# 393.net
KiCad netlist of a schematic drawn in EAGLE
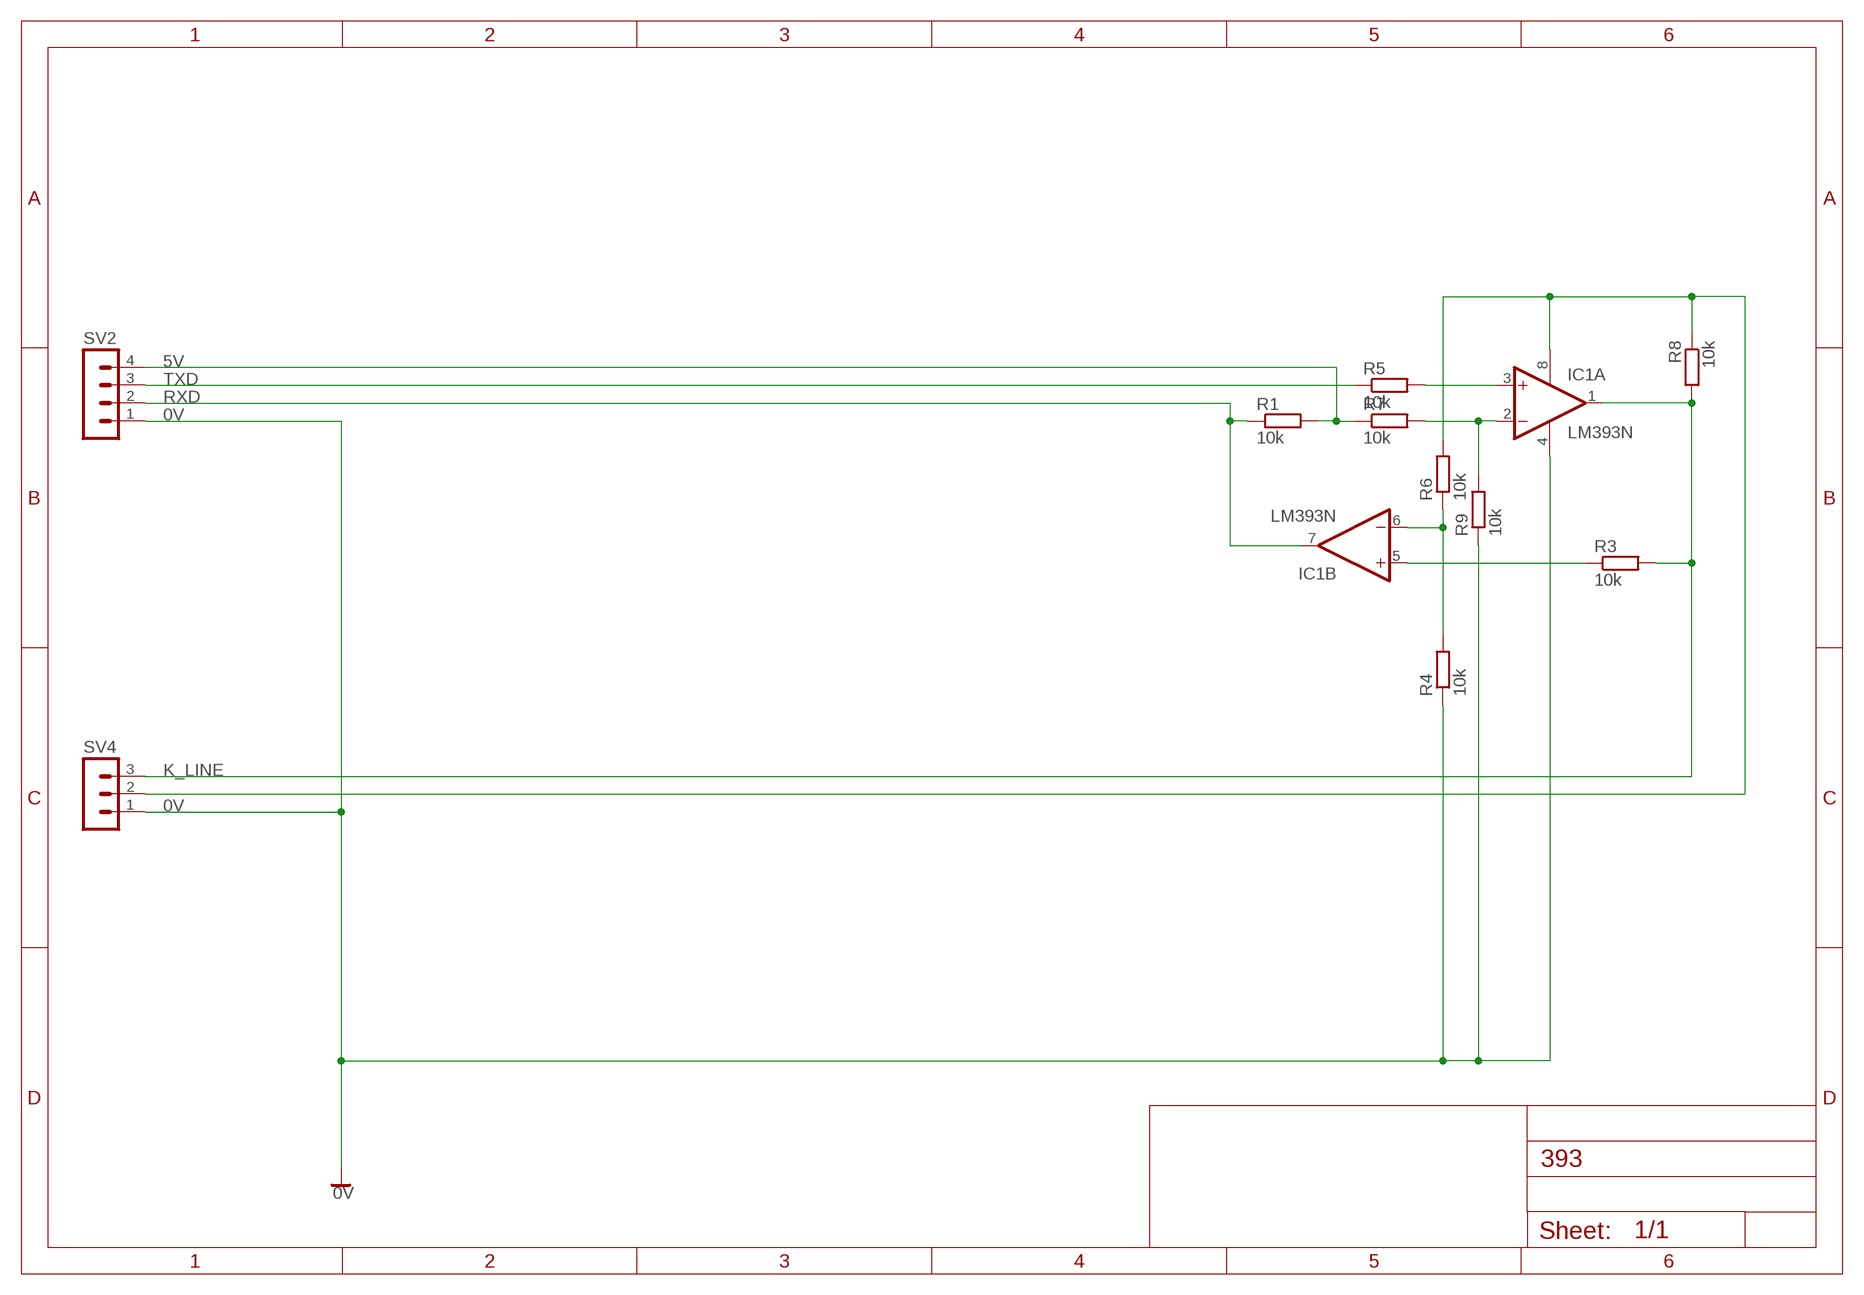
[diagram p0: schematic, sheet 1]

(export (version "E")
  (design (tool "Eeschema 10.0.6"))
  (components
    (comp (ref "IC1")
      (value "LM393N")
      (footprint "eagle-import:DIL08")
      (libsource (lib "eagle-import") (part "LM393N"))
    )
    (comp (ref "R1")
      (value "10k")
      (footprint "eagle-import:0207_7")
      (libsource (lib "eagle-import") (part "R-EU_0207/7"))
    )
    (comp (ref "R3")
      (value "10k")
      (footprint "eagle-import:0207_7")
      (libsource (lib "eagle-import") (part "R-EU_0207/7"))
    )
    (comp (ref "R4")
      (value "10k")
      (footprint "eagle-import:0207_7")
      (libsource (lib "eagle-import") (part "R-EU_0207/7"))
    )
    (comp (ref "R5")
      (value "10k")
      (footprint "eagle-import:0207_7")
      (libsource (lib "eagle-import") (part "R-EU_0207/7"))
    )
    (comp (ref "R6")
      (value "10k")
      (footprint "eagle-import:0207_7")
      (libsource (lib "eagle-import") (part "R-EU_0207/7"))
    )
    (comp (ref "R7")
      (value "10k")
      (footprint "eagle-import:0207_7")
      (libsource (lib "eagle-import") (part "R-EU_0207/7"))
    )
    (comp (ref "R8")
      (value "10k")
      (footprint "eagle-import:0207_7")
      (libsource (lib "eagle-import") (part "R-EU_0207/7"))
    )
    (comp (ref "R9")
      (value "10k")
      (footprint "eagle-import:0207_7")
      (libsource (lib "eagle-import") (part "R-EU_0207/7"))
    )
    (comp (ref "SV2")
      (value "MA04-1")
      (footprint "eagle-import:MA04-1")
      (libsource (lib "eagle-import") (part "MA04-1"))
    )
    (comp (ref "SV4")
      (value "MA03-1")
      (footprint "eagle-import:MA03-1")
      (libsource (lib "eagle-import") (part "MA03-1"))
    )
  )
  (nets
    (net (code "1") (name "/5V") (class "Default")
      (node (ref "R1") (pin "2") (pinfunction "2_2") (pintype "passive"))
      (node (ref "R7") (pin "1") (pinfunction "1_1") (pintype "passive"))
      (node (ref "SV2") (pin "4") (pinfunction "4_4") (pintype "passive"))
    )
    (net (code "2") (name "/K_LINE") (class "Default")
      (node (ref "IC1") (pin "1") (pinfunction "OUT_1") (pintype "output"))
      (node (ref "R3") (pin "2") (pinfunction "2_2") (pintype "passive"))
      (node (ref "R8") (pin "2") (pinfunction "2_2") (pintype "passive"))
      (node (ref "SV4") (pin "3") (pinfunction "3_3") (pintype "passive"))
    )
    (net (code "3") (name "/RXD") (class "Default")
      (node (ref "IC1") (pin "7") (pinfunction "OUT_7") (pintype "output"))
      (node (ref "R1") (pin "1") (pinfunction "1_1") (pintype "passive"))
      (node (ref "SV2") (pin "2") (pinfunction "2_2") (pintype "passive"))
    )
    (net (code "4") (name "/TXD") (class "Default")
      (node (ref "R5") (pin "1") (pinfunction "1_1") (pintype "passive"))
      (node (ref "SV2") (pin "3") (pinfunction "3_3") (pintype "passive"))
    )
    (net (code "5") (name "0V") (class "Default")
      (node (ref "IC1") (pin "4") (pinfunction "V-_4") (pintype "power_in"))
      (node (ref "R4") (pin "1") (pinfunction "1_1") (pintype "passive"))
      (node (ref "R9") (pin "1") (pinfunction "1_1") (pintype "passive"))
      (node (ref "SV2") (pin "1") (pinfunction "1_1") (pintype "passive"))
      (node (ref "SV4") (pin "1") (pinfunction "1_1") (pintype "passive"))
    )
    (net (code "6") (name "Net-(IC1A-+IN)") (class "Default")
      (node (ref "IC1") (pin "3") (pinfunction "+IN_3") (pintype "input"))
      (node (ref "R5") (pin "2") (pinfunction "2_2") (pintype "passive"))
    )
    (net (code "7") (name "Net-(IC1A--IN)") (class "Default")
      (node (ref "IC1") (pin "2") (pinfunction "-IN_2") (pintype "input"))
      (node (ref "R7") (pin "2") (pinfunction "2_2") (pintype "passive"))
      (node (ref "R9") (pin "2") (pinfunction "2_2") (pintype "passive"))
    )
    (net (code "8") (name "Net-(IC1B-+IN)") (class "Default")
      (node (ref "IC1") (pin "5") (pinfunction "+IN_5") (pintype "input"))
      (node (ref "R3") (pin "1") (pinfunction "1_1") (pintype "passive"))
    )
    (net (code "9") (name "Net-(IC1B--IN)") (class "Default")
      (node (ref "IC1") (pin "6") (pinfunction "-IN_6") (pintype "input"))
      (node (ref "R4") (pin "2") (pinfunction "2_2") (pintype "passive"))
      (node (ref "R6") (pin "1") (pinfunction "1_1") (pintype "passive"))
    )
    (net (code "10") (name "Net-(IC1C-V+)") (class "Default")
      (node (ref "IC1") (pin "8") (pinfunction "V+_8") (pintype "power_in"))
      (node (ref "R6") (pin "2") (pinfunction "2_2") (pintype "passive"))
      (node (ref "R8") (pin "1") (pinfunction "1_1") (pintype "passive"))
      (node (ref "SV4") (pin "2") (pinfunction "2_2") (pintype "passive"))
    )
  )
)
